# MidEthernet.net
KiCad netlist of a schematic drawn in Altium Designer
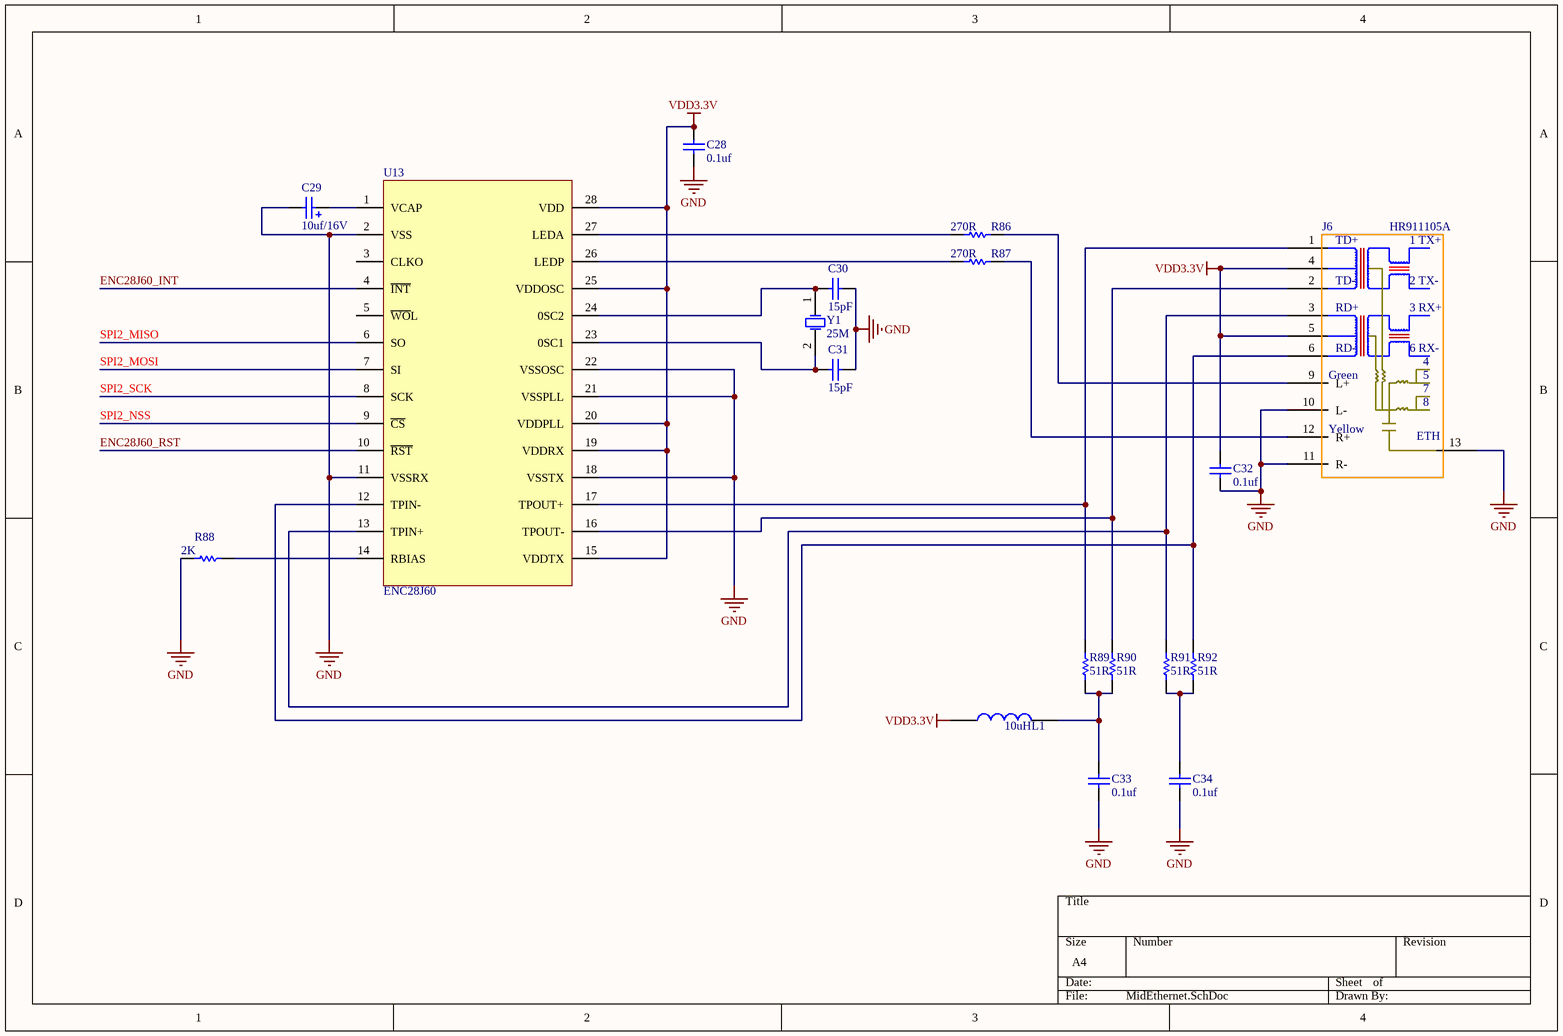
[diagram p0: MidEthernet.SchDoc]

(export (version "E")
  (design (tool "Eeschema 10.0.6"))
  (components
    (comp (ref "C28")
      (value "0.1uf")
      (footprint "C0805")
      (description "Capacitor")
      (fields
        (field (name "MANUFACTURER") "Generic Components")
        (field (name "Comment") "Cap")
        (field (name "PUBLISHER") "Altium Hobart Technology Centre")
      )
      (libsource (lib "Miscellaneous Devices") (part "Cap"))
    )
    (comp (ref "C29")
      (value "10uf/16V")
      (footprint "C3216")
      (description "Polarized Capacitor (Axial)")
      (fields (field (name "PUBLISHER") "Altium Limited"))
      (libsource (lib "Miscellaneous Devices") (part "Cap Pol2"))
    )
    (comp (ref "C30")
      (value "15pF")
      (footprint "C0805")
      (description "Capacitor")
      (fields (field (name "Comment") "Cap") (field (name "PUBLISHER") "Altium Limited"))
      (libsource (lib "Miscellaneous Devices") (part "Cap"))
    )
    (comp (ref "C31")
      (value "15pF")
      (footprint "C0805")
      (description "Capacitor")
      (fields (field (name "Comment") "Cap") (field (name "PUBLISHER") "Altium Limited"))
      (libsource (lib "Miscellaneous Devices") (part "Cap"))
    )
    (comp (ref "C32")
      (value "0.1uf")
      (footprint "C0805")
      (description "Capacitor")
      (fields
        (field (name "MANUFACTURER") "Generic Components")
        (field (name "Comment") "Cap")
        (field (name "PUBLISHER") "Altium Hobart Technology Centre")
      )
      (libsource (lib "Miscellaneous Devices") (part "Cap"))
    )
    (comp (ref "C33")
      (value "0.1uf")
      (footprint "C0805")
      (description "Capacitor")
      (fields
        (field (name "MANUFACTURER") "Generic Components")
        (field (name "Comment") "Cap")
        (field (name "PUBLISHER") "Altium Hobart Technology Centre")
      )
      (libsource (lib "Miscellaneous Devices") (part "Cap"))
    )
    (comp (ref "C34")
      (value "0.1uf")
      (footprint "C0805")
      (description "Capacitor")
      (fields
        (field (name "MANUFACTURER") "Generic Components")
        (field (name "Comment") "Cap")
        (field (name "PUBLISHER") "Altium Hobart Technology Centre")
      )
      (libsource (lib "Miscellaneous Devices") (part "Cap"))
    )
    (comp (ref "J6") (value "HR911105A") (footprint "HR911105A") (libsource (lib "*") (part "HR911102")))
    (comp (ref "L1") (value "10uH") (footprint "INDM4532N") (libsource (lib "电源板") (part "INDUCTOR")))
    (comp (ref "R86")
      (value "270R")
      (footprint "0805")
      (description "Semiconductor Resistor")
      (fields (field (name "Comment") "Res Semi") (field (name "PUBLISHER") "Altium Limited"))
      (libsource (lib "Miscellaneous Devices") (part "Res Semi"))
    )
    (comp (ref "R87")
      (value "270R")
      (footprint "0805")
      (description "Semiconductor Resistor")
      (fields (field (name "Comment") "Res Semi") (field (name "PUBLISHER") "Altium Limited"))
      (libsource (lib "Miscellaneous Devices") (part "Res Semi"))
    )
    (comp (ref "R88")
      (value "2K")
      (footprint "0805")
      (description "Semiconductor Resistor")
      (fields (field (name "Comment") "Res Semi") (field (name "PUBLISHER") "Altium Limited"))
      (libsource (lib "Miscellaneous Devices") (part "Res Semi"))
    )
    (comp (ref "R89")
      (value "51R")
      (footprint "0805")
      (description "Semiconductor Resistor")
      (fields (field (name "Comment") "Res Semi") (field (name "PUBLISHER") "Altium Limited"))
      (libsource (lib "Miscellaneous Devices") (part "Res Semi"))
    )
    (comp (ref "R90")
      (value "51R")
      (footprint "0805")
      (description "Semiconductor Resistor")
      (fields (field (name "Comment") "Res Semi") (field (name "PUBLISHER") "Altium Limited"))
      (libsource (lib "Miscellaneous Devices") (part "Res Semi"))
    )
    (comp (ref "R91")
      (value "51R")
      (footprint "0805")
      (description "Semiconductor Resistor")
      (fields (field (name "Comment") "Res Semi") (field (name "PUBLISHER") "Altium Limited"))
      (libsource (lib "Miscellaneous Devices") (part "Res Semi"))
    )
    (comp (ref "R92")
      (value "51R")
      (footprint "0805")
      (description "Semiconductor Resistor")
      (fields (field (name "Comment") "Res Semi") (field (name "PUBLISHER") "Altium Limited"))
      (libsource (lib "Miscellaneous Devices") (part "Res Semi"))
    )
    (comp (ref "U13") (value "ENC28J60") (footprint "SSOP28") (libsource (lib "常用器件库_SCH") (part "ENC28J60")))
    (comp (ref "Y1")
      (value "XTAL")
      (footprint "CY")
      (description "Crystal Oscillator")
      (fields (field (name "ALTIUM_UNNAMED_1") "25M") (field (name "PUBLISHER") "Altium Limited"))
      (libsource (lib "Miscellaneous Devices") (part "XTAL"))
    )
  )
  (nets
    (net (code "1") (name "/ENC28J60_INT") (class "Default")
      (node (ref "U13") (pin "4") (pinfunction "~{INT}_4") (pintype "passive"))
    )
    (net (code "2") (name "/ENC28J60_RST") (class "Default")
      (node (ref "U13") (pin "10") (pinfunction "~{RST}_10") (pintype "passive"))
    )
    (net (code "3") (name "/SPI2_MISO") (class "Default")
      (node (ref "U13") (pin "6") (pinfunction "SO_6") (pintype "passive"))
    )
    (net (code "4") (name "/SPI2_MOSI") (class "Default")
      (node (ref "U13") (pin "7") (pinfunction "SI_7") (pintype "passive"))
    )
    (net (code "5") (name "/SPI2_NSS") (class "Default")
      (node (ref "U13") (pin "9") (pinfunction "~{CS}_9") (pintype "passive"))
    )
    (net (code "6") (name "/SPI2_SCK") (class "Default")
      (node (ref "U13") (pin "8") (pinfunction "SCK_8") (pintype "passive"))
    )
    (net (code "7") (name "GND") (class "Default")
      (node (ref "C28") (pin "1") (pinfunction "1_1") (pintype "passive"))
      (node (ref "C29") (pin "2") (pinfunction "2_2") (pintype "passive"))
      (node (ref "C30") (pin "1") (pinfunction "1_1") (pintype "passive"))
      (node (ref "C31") (pin "1") (pinfunction "1_1") (pintype "passive"))
      (node (ref "C32") (pin "1") (pinfunction "1_1") (pintype "passive"))
      (node (ref "C33") (pin "1") (pinfunction "1_1") (pintype "passive"))
      (node (ref "C34") (pin "1") (pinfunction "1_1") (pintype "passive"))
      (node (ref "J6") (pin "10") (pinfunction "L-_10") (pintype "passive"))
      (node (ref "J6") (pin "11") (pinfunction "R-_11") (pintype "passive"))
      (node (ref "J6") (pin "13") (pintype "passive"))
      (node (ref "R88") (pin "2") (pinfunction "2_2") (pintype "passive"))
      (node (ref "U13") (pin "11") (pinfunction "VSSRX_11") (pintype "passive"))
      (node (ref "U13") (pin "18") (pinfunction "VSSTX_18") (pintype "passive"))
      (node (ref "U13") (pin "2") (pinfunction "VSS_2") (pintype "passive"))
      (node (ref "U13") (pin "21") (pinfunction "VSSPLL_21") (pintype "passive"))
      (node (ref "U13") (pin "22") (pinfunction "VSSOSC_22") (pintype "passive"))
    )
    (net (code "8") (name "Net-(C33-Pad2)") (class "Default")
      (node (ref "C33") (pin "2") (pinfunction "2_2") (pintype "passive"))
      (node (ref "L1") (pin "2") (pinfunction "2_2") (pintype "passive"))
      (node (ref "R89") (pin "2") (pinfunction "2_2") (pintype "passive"))
      (node (ref "R90") (pin "2") (pinfunction "2_2") (pintype "passive"))
    )
    (net (code "9") (name "Net-(C34-Pad2)") (class "Default")
      (node (ref "C34") (pin "2") (pinfunction "2_2") (pintype "passive"))
      (node (ref "R91") (pin "2") (pinfunction "2_2") (pintype "passive"))
      (node (ref "R92") (pin "2") (pinfunction "2_2") (pintype "passive"))
    )
    (net (code "10") (name "Net-(J6-L+)") (class "Default")
      (node (ref "J6") (pin "9") (pinfunction "L+_9") (pintype "passive"))
      (node (ref "R86") (pin "1") (pinfunction "1_1") (pintype "passive"))
    )
    (net (code "11") (name "Net-(J6-R+)") (class "Default")
      (node (ref "J6") (pin "12") (pinfunction "R+_12") (pintype "passive"))
      (node (ref "R87") (pin "1") (pinfunction "1_1") (pintype "passive"))
    )
    (net (code "12") (name "Net-(U13-0SC1)") (class "Default")
      (node (ref "C31") (pin "2") (pinfunction "2_2") (pintype "passive"))
      (node (ref "U13") (pin "23") (pinfunction "0SC1_23") (pintype "passive"))
      (node (ref "Y1") (pin "2") (pinfunction "OSC2_2") (pintype "passive"))
    )
    (net (code "13") (name "Net-(U13-0SC2)") (class "Default")
      (node (ref "C30") (pin "2") (pinfunction "2_2") (pintype "passive"))
      (node (ref "U13") (pin "24") (pinfunction "0SC2_24") (pintype "passive"))
      (node (ref "Y1") (pin "1") (pinfunction "OSC1_1") (pintype "passive"))
    )
    (net (code "14") (name "Net-(U13-LEDA)") (class "Default")
      (node (ref "R86") (pin "2") (pinfunction "2_2") (pintype "passive"))
      (node (ref "U13") (pin "27") (pinfunction "LEDA_27") (pintype "passive"))
    )
    (net (code "15") (name "Net-(U13-LEDP)") (class "Default")
      (node (ref "R87") (pin "2") (pinfunction "2_2") (pintype "passive"))
      (node (ref "U13") (pin "26") (pinfunction "LEDP_26") (pintype "passive"))
    )
    (net (code "16") (name "Net-(U13-RBIAS)") (class "Default")
      (node (ref "R88") (pin "1") (pinfunction "1_1") (pintype "passive"))
      (node (ref "U13") (pin "14") (pinfunction "RBIAS_14") (pintype "passive"))
    )
    (net (code "17") (name "Net-(U13-TPIN+)") (class "Default")
      (node (ref "J6") (pin "3") (pintype "passive"))
      (node (ref "R91") (pin "1") (pinfunction "1_1") (pintype "passive"))
      (node (ref "U13") (pin "13") (pinfunction "TPIN+_13") (pintype "passive"))
    )
    (net (code "18") (name "Net-(U13-TPIN-)") (class "Default")
      (node (ref "J6") (pin "6") (pintype "passive"))
      (node (ref "R92") (pin "1") (pinfunction "1_1") (pintype "passive"))
      (node (ref "U13") (pin "12") (pinfunction "TPIN-_12") (pintype "passive"))
    )
    (net (code "19") (name "Net-(U13-TPOUT+)") (class "Default")
      (node (ref "J6") (pin "1") (pintype "passive"))
      (node (ref "R89") (pin "1") (pinfunction "1_1") (pintype "passive"))
      (node (ref "U13") (pin "17") (pinfunction "TPOUT+_17") (pintype "passive"))
    )
    (net (code "20") (name "Net-(U13-TPOUT-)") (class "Default")
      (node (ref "J6") (pin "2") (pintype "passive"))
      (node (ref "R90") (pin "1") (pinfunction "1_1") (pintype "passive"))
      (node (ref "U13") (pin "16") (pinfunction "TPOUT-_16") (pintype "passive"))
    )
    (net (code "21") (name "Net-(U13-VCAP)") (class "Default")
      (node (ref "C29") (pin "1") (pinfunction "1_1") (pintype "passive"))
      (node (ref "U13") (pin "1") (pinfunction "VCAP_1") (pintype "passive"))
    )
    (net (code "22") (name "VDD3.3V") (class "Default")
      (node (ref "C28") (pin "2") (pinfunction "2_2") (pintype "passive"))
      (node (ref "C32") (pin "2") (pinfunction "2_2") (pintype "passive"))
      (node (ref "J6") (pin "4") (pintype "passive"))
      (node (ref "J6") (pin "5") (pintype "passive"))
      (node (ref "L1") (pin "1") (pinfunction "1_1") (pintype "passive"))
      (node (ref "U13") (pin "15") (pinfunction "VDDTX_15") (pintype "passive"))
      (node (ref "U13") (pin "19") (pinfunction "VDDRX_19") (pintype "passive"))
      (node (ref "U13") (pin "20") (pinfunction "VDDPLL_20") (pintype "passive"))
      (node (ref "U13") (pin "25") (pinfunction "VDDOSC_25") (pintype "passive"))
      (node (ref "U13") (pin "28") (pinfunction "VDD_28") (pintype "passive"))
    )
    (net (code "23") (name "unconnected-(U13-CLKO-Pad3)") (class "Default")
      (node (ref "U13") (pin "3") (pinfunction "CLKO_3") (pintype "passive"))
    )
    (net (code "24") (name "unconnected-(U13-~{WO}L-Pad5)") (class "Default")
      (node (ref "U13") (pin "5") (pinfunction "~{WO}L_5") (pintype "passive"))
    )
  )
)
